# SchemaBloc.net
KiCad netlist of a schematic drawn in Altium Designer
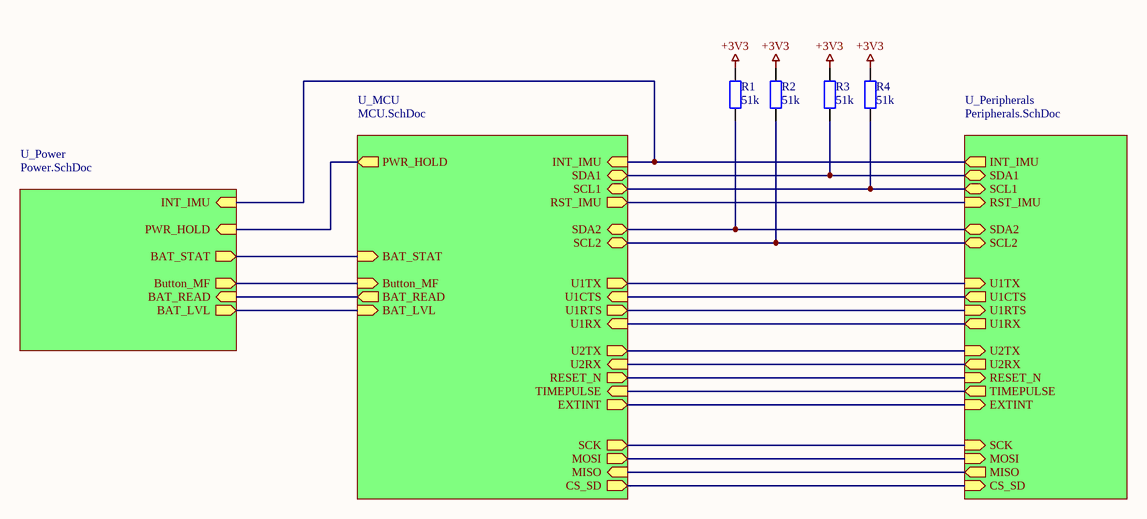
[diagram p0: SchemaBloc.SchDoc]

(export (version "E")
  (design (tool "Eeschema 10.0.6"))
  (components
    (comp (ref "R1")
      (value "51k")
      (footprint "RES_0805")
      (description "Res 0805")
      (fields (field (name "PUBLISHER") "Altium Limited"))
      (libsource (lib "Miscellaneous Devices") (part "Res2"))
    )
    (comp (ref "R2")
      (value "51k")
      (footprint "RES_0805")
      (description "Res 0805")
      (fields (field (name "PUBLISHER") "Altium Limited"))
      (libsource (lib "Miscellaneous Devices") (part "Res2"))
    )
    (comp (ref "R3")
      (value "51k")
      (footprint "RES_0805")
      (description "Res 0805")
      (fields (field (name "PUBLISHER") "Altium Limited"))
      (libsource (lib "Miscellaneous Devices") (part "Res2"))
    )
    (comp (ref "R4")
      (value "51k")
      (footprint "RES_0805")
      (description "Res 0805")
      (fields (field (name "PUBLISHER") "Altium Limited"))
      (libsource (lib "Miscellaneous Devices") (part "Res2"))
    )
  )
  (nets
    (net (code "1") (name "+3V3") (class "Default")
      (node (ref "R1") (pin "2") (pinfunction "2_2") (pintype "passive"))
      (node (ref "R2") (pin "2") (pinfunction "2_2") (pintype "passive"))
      (node (ref "R3") (pin "2") (pinfunction "2_2") (pintype "passive"))
      (node (ref "R4") (pin "2") (pinfunction "2_2") (pintype "passive"))
    )
    (net (code "15") (name "/SCL1") (class "Default")
      (node (ref "R4") (pin "1") (pinfunction "1_1") (pintype "passive"))
    )
    (net (code "16") (name "/SCL2") (class "Default")
      (node (ref "R2") (pin "1") (pinfunction "1_1") (pintype "passive"))
    )
    (net (code "17") (name "/SDA1") (class "Default")
      (node (ref "R3") (pin "1") (pinfunction "1_1") (pintype "passive"))
    )
    (net (code "18") (name "/SDA2") (class "Default")
      (node (ref "R1") (pin "1") (pinfunction "1_1") (pintype "passive"))
    )
  )
)
